# InterfacesA_RGMII_Ethernet.net
KiCad netlist of a schematic drawn in Altium Designer
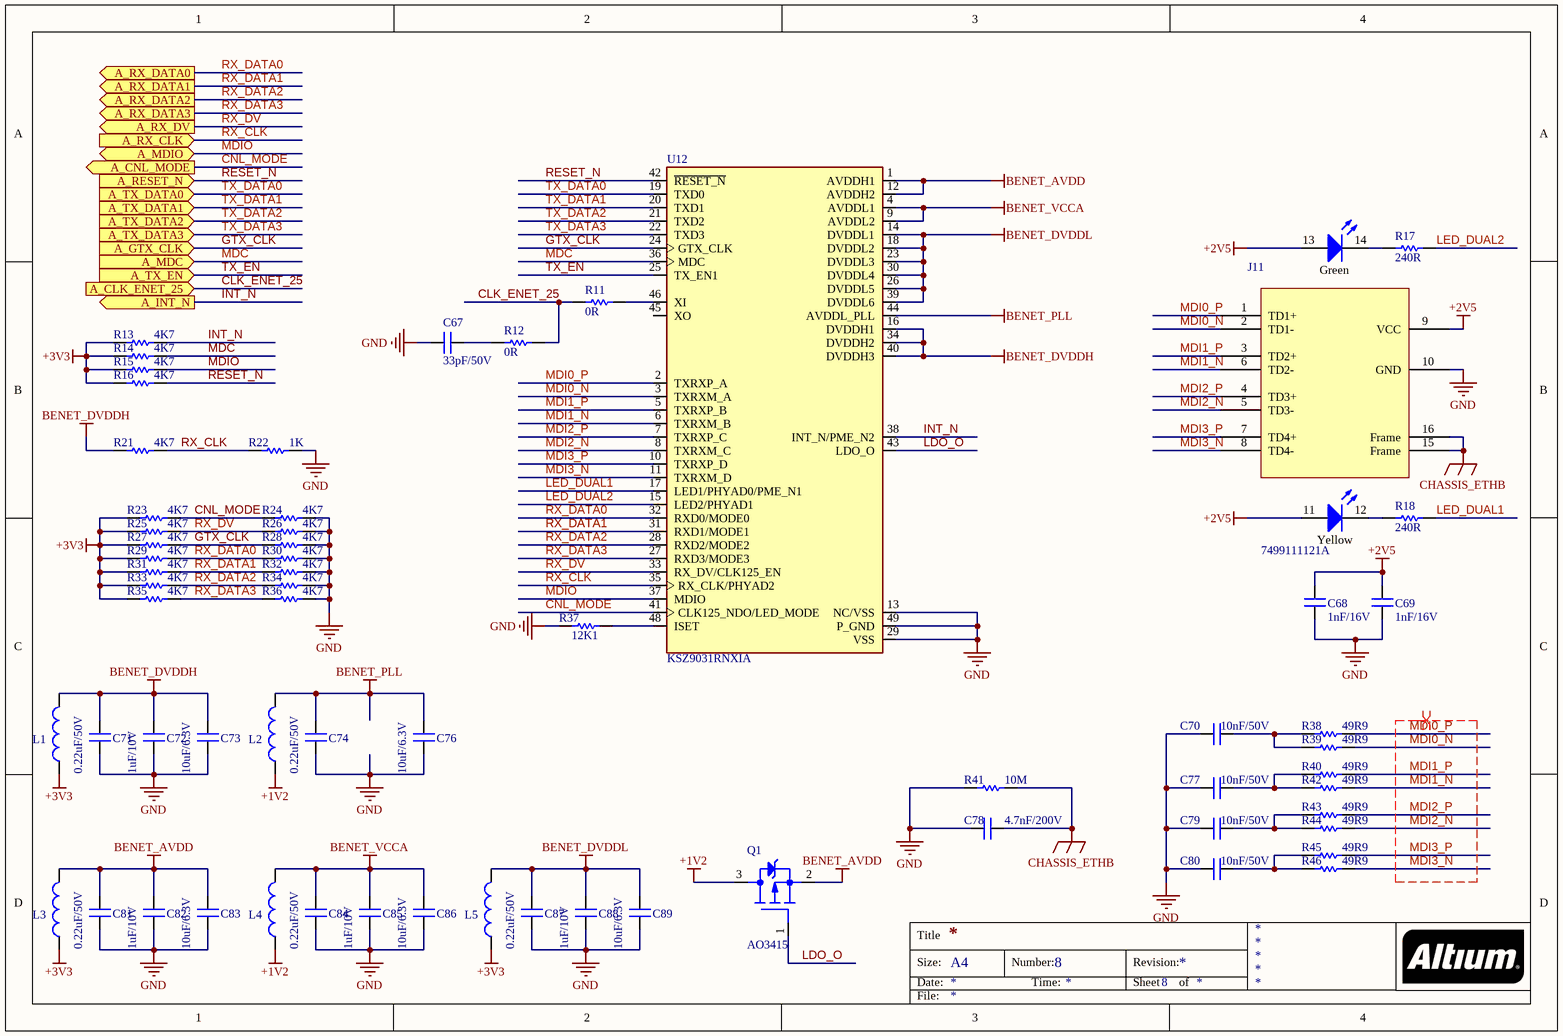
[diagram p0: InterfacesA_RGMII_Ethernet.SchDoc]

(export (version "E")
  (design (tool "Eeschema 10.0.6"))
  (components
    (comp (ref "C67")
      (value "33pF/50V")
      (footprint "CAP_0805")
      (fields (field (name "Comment") "CAP_0805"))
      (libsource (lib "AdapterLib") (part "CAP_0805"))
    )
    (comp (ref "C68")
      (value "1nF/16V")
      (footprint "CAP_0805")
      (fields (field (name "Comment") "CAP_0805"))
      (libsource (lib "AdapterLib") (part "CAP_0805"))
    )
    (comp (ref "C69")
      (value "1nF/16V")
      (footprint "CAP_0805")
      (fields (field (name "Comment") "CAP_0805"))
      (libsource (lib "AdapterLib") (part "CAP_0805"))
    )
    (comp (ref "C70")
      (value "10nF/50V")
      (footprint "CAP_0805")
      (fields (field (name "Comment") "CAP_0805"))
      (libsource (lib "AdapterLib") (part "CAP_0805"))
    )
    (comp (ref "C71")
      (value "0.22uF/50V")
      (footprint "CAP_0805")
      (fields (field (name "Comment") "CAP_0805"))
      (libsource (lib "AdapterLib") (part "CAP_0805"))
    )
    (comp (ref "C72")
      (value "1uF/10V")
      (footprint "CAP_0805")
      (fields (field (name "Comment") "CAP_0805"))
      (libsource (lib "AdapterLib") (part "CAP_0805"))
    )
    (comp (ref "C73")
      (value "10uF/6.3V")
      (footprint "CAP_0805")
      (fields (field (name "Comment") "CAP_0805"))
      (libsource (lib "AdapterLib") (part "CAP_0805"))
    )
    (comp (ref "C74")
      (value "0.22uF/50V")
      (footprint "CAP_0805")
      (fields (field (name "Comment") "CAP_0805"))
      (libsource (lib "AdapterLib") (part "CAP_0805"))
    )
    (comp (ref "C76")
      (value "10uF/6.3V")
      (footprint "CAP_0805")
      (fields (field (name "Comment") "CAP_0805"))
      (libsource (lib "AdapterLib") (part "CAP_0805"))
    )
    (comp (ref "C77")
      (value "10nF/50V")
      (footprint "CAP_0805")
      (fields (field (name "Comment") "CAP_0805"))
      (libsource (lib "AdapterLib") (part "CAP_0805"))
    )
    (comp (ref "C78")
      (value "4.7nF/200V")
      (footprint "CAP_0805")
      (fields (field (name "Comment") "CAP_0805"))
      (libsource (lib "AdapterLib") (part "CAP_0805"))
    )
    (comp (ref "C79")
      (value "10nF/50V")
      (footprint "CAP_0805")
      (fields (field (name "Comment") "CAP_0805"))
      (libsource (lib "AdapterLib") (part "CAP_0805"))
    )
    (comp (ref "C80")
      (value "10nF/50V")
      (footprint "CAP_0805")
      (fields (field (name "Comment") "CAP_0805"))
      (libsource (lib "AdapterLib") (part "CAP_0805"))
    )
    (comp (ref "C81")
      (value "0.22uF/50V")
      (footprint "CAP_0805")
      (fields (field (name "Comment") "CAP_0805"))
      (libsource (lib "AdapterLib") (part "CAP_0805"))
    )
    (comp (ref "C82")
      (value "1uF/10V")
      (footprint "CAP_0805")
      (fields (field (name "Comment") "CAP_0805"))
      (libsource (lib "AdapterLib") (part "CAP_0805"))
    )
    (comp (ref "C83")
      (value "10uF/6.3V")
      (footprint "CAP_0805")
      (fields (field (name "Comment") "CAP_0805"))
      (libsource (lib "AdapterLib") (part "CAP_0805"))
    )
    (comp (ref "C84")
      (value "0.22uF/50V")
      (footprint "CAP_0805")
      (fields (field (name "Comment") "CAP_0805"))
      (libsource (lib "AdapterLib") (part "CAP_0805"))
    )
    (comp (ref "C85")
      (value "1uF/10V")
      (footprint "CAP_0805")
      (fields (field (name "Comment") "CAP_0805"))
      (libsource (lib "AdapterLib") (part "CAP_0805"))
    )
    (comp (ref "C86")
      (value "10uF/6.3V")
      (footprint "CAP_0805")
      (fields (field (name "Comment") "CAP_0805"))
      (libsource (lib "AdapterLib") (part "CAP_0805"))
    )
    (comp (ref "C87")
      (value "0.22uF/50V")
      (footprint "CAP_0805")
      (fields (field (name "Comment") "CAP_0805"))
      (libsource (lib "AdapterLib") (part "CAP_0805"))
    )
    (comp (ref "C88")
      (value "1uF/10V")
      (footprint "CAP_0805")
      (fields (field (name "Comment") "CAP_0805"))
      (libsource (lib "AdapterLib") (part "CAP_0805"))
    )
    (comp (ref "C89")
      (value "10uF/6.3V")
      (footprint "CAP_0805")
      (fields (field (name "Comment") "CAP_0805"))
      (libsource (lib "AdapterLib") (part "CAP_0805"))
    )
    (comp (ref "J11")
      (value "7499111121A")
      (footprint "7499111121A")
      (libsource (lib "AdapterLib") (part "7499111121A"))
    )
    (comp (ref "L1")
      (value "IND_0805")
      (footprint "IND_0805")
      (libsource (lib "AdapterLib") (part "IND_0805"))
    )
    (comp (ref "L2")
      (value "IND_0805")
      (footprint "IND_0805")
      (libsource (lib "AdapterLib") (part "IND_0805"))
    )
    (comp (ref "L3")
      (value "IND_0805")
      (footprint "IND_0805")
      (libsource (lib "AdapterLib") (part "IND_0805"))
    )
    (comp (ref "L4")
      (value "IND_0805")
      (footprint "IND_0805")
      (libsource (lib "AdapterLib") (part "IND_0805"))
    )
    (comp (ref "L5")
      (value "IND_0805")
      (footprint "IND_0805")
      (libsource (lib "AdapterLib") (part "IND_0805"))
    )
    (comp (ref "Q1")
      (value "AO3415")
      (footprint "AO3415")
      (description "20V P-Channel MOSFET")
      (libsource (lib "AdapterLib") (part "AO3415"))
    )
    (comp (ref "R11")
      (value "0R")
      (footprint "RES_0805")
      (fields (field (name "Comment") "RES_0805"))
      (libsource (lib "AdapterLib") (part "RES_0805"))
    )
    (comp (ref "R12")
      (value "0R")
      (footprint "RES_0805")
      (fields (field (name "Comment") "RES_0805"))
      (libsource (lib "AdapterLib") (part "RES_0805"))
    )
    (comp (ref "R13")
      (value "4K7")
      (footprint "RES_0805")
      (fields (field (name "Comment") "RES_0805"))
      (libsource (lib "AdapterLib") (part "RES_0805"))
    )
    (comp (ref "R14")
      (value "4K7")
      (footprint "RES_0805")
      (fields (field (name "Comment") "RES_0805"))
      (libsource (lib "AdapterLib") (part "RES_0805"))
    )
    (comp (ref "R15")
      (value "4K7")
      (footprint "RES_0805")
      (fields (field (name "Comment") "RES_0805"))
      (libsource (lib "AdapterLib") (part "RES_0805"))
    )
    (comp (ref "R16")
      (value "4K7")
      (footprint "RES_0805")
      (fields (field (name "Comment") "RES_0805"))
      (libsource (lib "AdapterLib") (part "RES_0805"))
    )
    (comp (ref "R17")
      (value "240R")
      (footprint "RES_0805")
      (fields (field (name "Comment") "RES_0805"))
      (libsource (lib "AdapterLib") (part "RES_0805"))
    )
    (comp (ref "R18")
      (value "240R")
      (footprint "RES_0805")
      (fields (field (name "Comment") "RES_0805"))
      (libsource (lib "AdapterLib") (part "RES_0805"))
    )
    (comp (ref "R21")
      (value "4K7")
      (footprint "RES_0805")
      (fields (field (name "Comment") "RES_0805"))
      (libsource (lib "AdapterLib") (part "RES_0805"))
    )
    (comp (ref "R22")
      (value "1K")
      (footprint "RES_0805")
      (fields (field (name "Comment") "RES_0805"))
      (libsource (lib "AdapterLib") (part "RES_0805"))
    )
    (comp (ref "R23")
      (value "4K7")
      (footprint "RES_0805")
      (fields (field (name "Comment") "RES_0805"))
      (libsource (lib "AdapterLib") (part "RES_0805"))
    )
    (comp (ref "R24")
      (value "4K7")
      (footprint "RES_0805")
      (fields (field (name "Comment") "RES_0805"))
      (libsource (lib "AdapterLib") (part "RES_0805"))
    )
    (comp (ref "R25")
      (value "4K7")
      (footprint "RES_0805")
      (fields (field (name "Comment") "RES_0805"))
      (libsource (lib "AdapterLib") (part "RES_0805"))
    )
    (comp (ref "R26")
      (value "4K7")
      (footprint "RES_0805")
      (fields (field (name "Comment") "RES_0805"))
      (libsource (lib "AdapterLib") (part "RES_0805"))
    )
    (comp (ref "R27")
      (value "4K7")
      (footprint "RES_0805")
      (fields (field (name "Comment") "RES_0805"))
      (libsource (lib "AdapterLib") (part "RES_0805"))
    )
    (comp (ref "R28")
      (value "4K7")
      (footprint "RES_0805")
      (fields (field (name "Comment") "RES_0805"))
      (libsource (lib "AdapterLib") (part "RES_0805"))
    )
    (comp (ref "R29")
      (value "4K7")
      (footprint "RES_0805")
      (fields (field (name "Comment") "RES_0805"))
      (libsource (lib "AdapterLib") (part "RES_0805"))
    )
    (comp (ref "R30")
      (value "4K7")
      (footprint "RES_0805")
      (fields (field (name "Comment") "RES_0805"))
      (libsource (lib "AdapterLib") (part "RES_0805"))
    )
    (comp (ref "R31")
      (value "4K7")
      (footprint "RES_0805")
      (fields (field (name "Comment") "RES_0805"))
      (libsource (lib "AdapterLib") (part "RES_0805"))
    )
    (comp (ref "R32")
      (value "4K7")
      (footprint "RES_0805")
      (fields (field (name "Comment") "RES_0805"))
      (libsource (lib "AdapterLib") (part "RES_0805"))
    )
    (comp (ref "R33")
      (value "4K7")
      (footprint "RES_0805")
      (fields (field (name "Comment") "RES_0805"))
      (libsource (lib "AdapterLib") (part "RES_0805"))
    )
    (comp (ref "R34")
      (value "4K7")
      (footprint "RES_0805")
      (fields (field (name "Comment") "RES_0805"))
      (libsource (lib "AdapterLib") (part "RES_0805"))
    )
    (comp (ref "R35")
      (value "4K7")
      (footprint "RES_0805")
      (fields (field (name "Comment") "RES_0805"))
      (libsource (lib "AdapterLib") (part "RES_0805"))
    )
    (comp (ref "R36")
      (value "4K7")
      (footprint "RES_0805")
      (fields (field (name "Comment") "RES_0805"))
      (libsource (lib "AdapterLib") (part "RES_0805"))
    )
    (comp (ref "R37")
      (value "12K1")
      (footprint "RES_0805")
      (fields (field (name "Comment") "RES_0805"))
      (libsource (lib "AdapterLib") (part "RES_0805"))
    )
    (comp (ref "R38")
      (value "49R9")
      (footprint "RES_0805")
      (fields (field (name "Comment") "RES_0805"))
      (libsource (lib "AdapterLib") (part "RES_0805"))
    )
    (comp (ref "R39")
      (value "49R9")
      (footprint "RES_0805")
      (fields (field (name "Comment") "RES_0805"))
      (libsource (lib "AdapterLib") (part "RES_0805"))
    )
    (comp (ref "R40")
      (value "49R9")
      (footprint "RES_0805")
      (fields (field (name "Comment") "RES_0805"))
      (libsource (lib "AdapterLib") (part "RES_0805"))
    )
    (comp (ref "R41")
      (value "10M")
      (footprint "RES_0805")
      (fields (field (name "Comment") "RES_0805"))
      (libsource (lib "AdapterLib") (part "RES_0805"))
    )
    (comp (ref "R42")
      (value "49R9")
      (footprint "RES_0805")
      (fields (field (name "Comment") "RES_0805"))
      (libsource (lib "AdapterLib") (part "RES_0805"))
    )
    (comp (ref "R43")
      (value "49R9")
      (footprint "RES_0805")
      (fields (field (name "Comment") "RES_0805"))
      (libsource (lib "AdapterLib") (part "RES_0805"))
    )
    (comp (ref "R44")
      (value "49R9")
      (footprint "RES_0805")
      (fields (field (name "Comment") "RES_0805"))
      (libsource (lib "AdapterLib") (part "RES_0805"))
    )
    (comp (ref "R45")
      (value "49R9")
      (footprint "RES_0805")
      (fields (field (name "Comment") "RES_0805"))
      (libsource (lib "AdapterLib") (part "RES_0805"))
    )
    (comp (ref "R46")
      (value "49R9")
      (footprint "RES_0805")
      (fields (field (name "Comment") "RES_0805"))
      (libsource (lib "AdapterLib") (part "RES_0805"))
    )
    (comp (ref "U12")
      (value "KSZ9031RNXIA")
      (footprint "AdapterLib:KSZ9031RNXIA")
      (description "4/4 Transceiver Full Ethernet 48-QFN _7x7_")
      (fields (field (name "DIGI-KEY_PART_NUMBER") "KSZ9031RNXIA-TR-ND") (field (name "MF") "Microchip"))
      (libsource (lib "AdapterLib") (part "KSZ9031RNXIA"))
    )
  )
  (nets
    (net (code "1") (name "+1V2") (class "Default")
      (node (ref "L2") (pin "1") (pinfunction "1_1") (pintype "passive"))
      (node (ref "L4") (pin "1") (pinfunction "1_1") (pintype "passive"))
      (node (ref "Q1") (pin "3") (pinfunction "D_3") (pintype "passive"))
    )
    (net (code "2") (name "+2V5") (class "Default")
      (node (ref "C68") (pin "2") (pinfunction "2_2") (pintype "passive"))
      (node (ref "C69") (pin "2") (pinfunction "2_2") (pintype "passive"))
      (node (ref "J11") (pin "11") (pinfunction "A_11") (pintype "passive"))
      (node (ref "J11") (pin "13") (pinfunction "A_13") (pintype "passive"))
      (node (ref "J11") (pin "9") (pinfunction "VCC_9") (pintype "passive"))
    )
    (net (code "3") (name "+3V3") (class "Default")
      (node (ref "L1") (pin "1") (pinfunction "1_1") (pintype "passive"))
      (node (ref "L3") (pin "1") (pinfunction "1_1") (pintype "passive"))
      (node (ref "L5") (pin "1") (pinfunction "1_1") (pintype "passive"))
      (node (ref "R13") (pin "2") (pinfunction "2_2") (pintype "passive"))
      (node (ref "R14") (pin "2") (pinfunction "2_2") (pintype "passive"))
      (node (ref "R15") (pin "2") (pinfunction "2_2") (pintype "passive"))
      (node (ref "R16") (pin "2") (pinfunction "2_2") (pintype "passive"))
      (node (ref "R23") (pin "2") (pinfunction "2_2") (pintype "passive"))
      (node (ref "R25") (pin "2") (pinfunction "2_2") (pintype "passive"))
      (node (ref "R27") (pin "2") (pinfunction "2_2") (pintype "passive"))
      (node (ref "R29") (pin "2") (pinfunction "2_2") (pintype "passive"))
      (node (ref "R31") (pin "2") (pinfunction "2_2") (pintype "passive"))
      (node (ref "R33") (pin "2") (pinfunction "2_2") (pintype "passive"))
      (node (ref "R35") (pin "2") (pinfunction "2_2") (pintype "passive"))
    )
    (net (code "4") (name "/CLK_ENET_25") (class "Default")
      (node (ref "R11") (pin "2") (pinfunction "2_2") (pintype "passive"))
      (node (ref "R12") (pin "2") (pinfunction "2_2") (pintype "passive"))
    )
    (net (code "5") (name "/CNL_MODE") (class "Default")
      (node (ref "R23") (pin "1") (pinfunction "1_1") (pintype "passive"))
      (node (ref "R24") (pin "2") (pinfunction "2_2") (pintype "passive"))
      (node (ref "U12") (pin "41") (pinfunction "CLK125_NDO/LED_MODE_41") (pintype "passive"))
    )
    (net (code "6") (name "/GTX_CLK") (class "Default")
      (node (ref "R27") (pin "1") (pinfunction "1_1") (pintype "passive"))
      (node (ref "R28") (pin "2") (pinfunction "2_2") (pintype "passive"))
      (node (ref "U12") (pin "24") (pinfunction "GTX_CLK_24") (pintype "passive"))
    )
    (net (code "7") (name "/INT_N") (class "Default")
      (node (ref "R13") (pin "1") (pinfunction "1_1") (pintype "passive"))
      (node (ref "U12") (pin "38") (pinfunction "INT_N/PME_N2_38") (pintype "passive"))
    )
    (net (code "8") (name "/LDO_O") (class "Default")
      (node (ref "Q1") (pin "1") (pinfunction "G_1") (pintype "passive"))
      (node (ref "U12") (pin "43") (pinfunction "LDO_O_43") (pintype "passive"))
    )
    (net (code "9") (name "/LED_DUAL1") (class "Default")
      (node (ref "R18") (pin "2") (pinfunction "2_2") (pintype "passive"))
      (node (ref "U12") (pin "17") (pinfunction "LED1/PHYAD0/PME_N1_17") (pintype "passive"))
    )
    (net (code "10") (name "/LED_DUAL2") (class "Default")
      (node (ref "R17") (pin "2") (pinfunction "2_2") (pintype "passive"))
      (node (ref "U12") (pin "15") (pinfunction "LED2/PHYAD1_15") (pintype "passive"))
    )
    (net (code "11") (name "/MDC") (class "Default")
      (node (ref "R14") (pin "1") (pinfunction "1_1") (pintype "passive"))
      (node (ref "U12") (pin "36") (pinfunction "MDC_36") (pintype "passive"))
    )
    (net (code "12") (name "/MDI0_N") (class "Default")
      (node (ref "J11") (pin "2") (pinfunction "TD1-_2") (pintype "passive"))
      (node (ref "R39") (pin "2") (pinfunction "2_2") (pintype "passive"))
      (node (ref "U12") (pin "3") (pinfunction "TXRXM_A_3") (pintype "passive"))
    )
    (net (code "13") (name "/MDI0_P") (class "Default")
      (node (ref "J11") (pin "1") (pinfunction "TD1+_1") (pintype "passive"))
      (node (ref "R38") (pin "2") (pinfunction "2_2") (pintype "passive"))
      (node (ref "U12") (pin "2") (pinfunction "TXRXP_A_2") (pintype "passive"))
    )
    (net (code "14") (name "/MDI1_N") (class "Default")
      (node (ref "J11") (pin "6") (pinfunction "TD2-_6") (pintype "passive"))
      (node (ref "R42") (pin "2") (pinfunction "2_2") (pintype "passive"))
      (node (ref "U12") (pin "6") (pinfunction "TXRXM_B_6") (pintype "passive"))
    )
    (net (code "15") (name "/MDI1_P") (class "Default")
      (node (ref "J11") (pin "3") (pinfunction "TD2+_3") (pintype "passive"))
      (node (ref "R40") (pin "2") (pinfunction "2_2") (pintype "passive"))
      (node (ref "U12") (pin "5") (pinfunction "TXRXP_B_5") (pintype "passive"))
    )
    (net (code "16") (name "/MDI2_N") (class "Default")
      (node (ref "J11") (pin "5") (pinfunction "TD3-_5") (pintype "passive"))
      (node (ref "R44") (pin "2") (pinfunction "2_2") (pintype "passive"))
      (node (ref "U12") (pin "8") (pinfunction "TXRXM_C_8") (pintype "passive"))
    )
    (net (code "17") (name "/MDI2_P") (class "Default")
      (node (ref "J11") (pin "4") (pinfunction "TD3+_4") (pintype "passive"))
      (node (ref "R43") (pin "2") (pinfunction "2_2") (pintype "passive"))
      (node (ref "U12") (pin "7") (pinfunction "TXRXP_C_7") (pintype "passive"))
    )
    (net (code "18") (name "/MDI3_N") (class "Default")
      (node (ref "J11") (pin "8") (pinfunction "TD4-_8") (pintype "passive"))
      (node (ref "R46") (pin "2") (pinfunction "2_2") (pintype "passive"))
      (node (ref "U12") (pin "11") (pinfunction "TXRXM_D_11") (pintype "passive"))
    )
    (net (code "19") (name "/MDI3_P") (class "Default")
      (node (ref "J11") (pin "7") (pinfunction "TD4+_7") (pintype "passive"))
      (node (ref "R45") (pin "2") (pinfunction "2_2") (pintype "passive"))
      (node (ref "U12") (pin "10") (pinfunction "TXRXP_D_10") (pintype "passive"))
    )
    (net (code "20") (name "/MDIO") (class "Default")
      (node (ref "R15") (pin "1") (pinfunction "1_1") (pintype "passive"))
      (node (ref "U12") (pin "37") (pinfunction "MDIO_37") (pintype "passive"))
    )
    (net (code "21") (name "/RESET_N") (class "Default")
      (node (ref "R16") (pin "1") (pinfunction "1_1") (pintype "passive"))
      (node (ref "U12") (pin "42") (pinfunction "~{RESET_N}_42") (pintype "passive"))
    )
    (net (code "22") (name "/RX_CLK") (class "Default")
      (node (ref "R21") (pin "1") (pinfunction "1_1") (pintype "passive"))
      (node (ref "R22") (pin "2") (pinfunction "2_2") (pintype "passive"))
      (node (ref "U12") (pin "35") (pinfunction "RX_CLK/PHYAD2_35") (pintype "passive"))
    )
    (net (code "23") (name "/RX_DATA0") (class "Default")
      (node (ref "R29") (pin "1") (pinfunction "1_1") (pintype "passive"))
      (node (ref "R30") (pin "2") (pinfunction "2_2") (pintype "passive"))
      (node (ref "U12") (pin "32") (pinfunction "RXD0/MODE0_32") (pintype "passive"))
    )
    (net (code "24") (name "/RX_DATA1") (class "Default")
      (node (ref "R31") (pin "1") (pinfunction "1_1") (pintype "passive"))
      (node (ref "R32") (pin "2") (pinfunction "2_2") (pintype "passive"))
      (node (ref "U12") (pin "31") (pinfunction "RXD1/MODE1_31") (pintype "passive"))
    )
    (net (code "25") (name "/RX_DATA2") (class "Default")
      (node (ref "R33") (pin "1") (pinfunction "1_1") (pintype "passive"))
      (node (ref "R34") (pin "2") (pinfunction "2_2") (pintype "passive"))
      (node (ref "U12") (pin "28") (pinfunction "RXD2/MODE2_28") (pintype "passive"))
    )
    (net (code "26") (name "/RX_DATA3") (class "Default")
      (node (ref "R35") (pin "1") (pinfunction "1_1") (pintype "passive"))
      (node (ref "R36") (pin "2") (pinfunction "2_2") (pintype "passive"))
      (node (ref "U12") (pin "27") (pinfunction "RXD3/MODE3_27") (pintype "passive"))
    )
    (net (code "27") (name "/RX_DV") (class "Default")
      (node (ref "R25") (pin "1") (pinfunction "1_1") (pintype "passive"))
      (node (ref "R26") (pin "2") (pinfunction "2_2") (pintype "passive"))
      (node (ref "U12") (pin "33") (pinfunction "RX_DV/CLK125_EN_33") (pintype "passive"))
    )
    (net (code "28") (name "/TX_DATA0") (class "Default")
      (node (ref "U12") (pin "19") (pinfunction "TXD0_19") (pintype "passive"))
    )
    (net (code "29") (name "/TX_DATA1") (class "Default")
      (node (ref "U12") (pin "20") (pinfunction "TXD1_20") (pintype "passive"))
    )
    (net (code "30") (name "/TX_DATA2") (class "Default")
      (node (ref "U12") (pin "21") (pinfunction "TXD2_21") (pintype "passive"))
    )
    (net (code "31") (name "/TX_DATA3") (class "Default")
      (node (ref "U12") (pin "22") (pinfunction "TXD3_22") (pintype "passive"))
    )
    (net (code "32") (name "/TX_EN") (class "Default")
      (node (ref "U12") (pin "25") (pinfunction "TX_EN1_25") (pintype "passive"))
    )
    (net (code "33") (name "BENET_AVDD") (class "Default")
      (node (ref "C81") (pin "2") (pinfunction "2_2") (pintype "passive"))
      (node (ref "C82") (pin "2") (pinfunction "2_2") (pintype "passive"))
      (node (ref "C83") (pin "2") (pinfunction "2_2") (pintype "passive"))
      (node (ref "L3") (pin "2") (pinfunction "2_2") (pintype "passive"))
      (node (ref "Q1") (pin "2") (pinfunction "S_2") (pintype "passive"))
      (node (ref "U12") (pin "1") (pinfunction "AVDDH1_1") (pintype "passive"))
      (node (ref "U12") (pin "12") (pinfunction "AVDDH2_12") (pintype "passive"))
    )
    (net (code "34") (name "BENET_DVDDH") (class "Default")
      (node (ref "C71") (pin "2") (pinfunction "2_2") (pintype "passive"))
      (node (ref "C72") (pin "2") (pinfunction "2_2") (pintype "passive"))
      (node (ref "C73") (pin "2") (pinfunction "2_2") (pintype "passive"))
      (node (ref "L1") (pin "2") (pinfunction "2_2") (pintype "passive"))
      (node (ref "R21") (pin "2") (pinfunction "2_2") (pintype "passive"))
      (node (ref "U12") (pin "16") (pinfunction "DVDDH1_16") (pintype "passive"))
      (node (ref "U12") (pin "34") (pinfunction "DVDDH2_34") (pintype "passive"))
      (node (ref "U12") (pin "40") (pinfunction "DVDDH3_40") (pintype "passive"))
    )
    (net (code "35") (name "BENET_DVDDL") (class "Default")
      (node (ref "C87") (pin "2") (pinfunction "2_2") (pintype "passive"))
      (node (ref "C88") (pin "2") (pinfunction "2_2") (pintype "passive"))
      (node (ref "C89") (pin "2") (pinfunction "2_2") (pintype "passive"))
      (node (ref "L5") (pin "2") (pinfunction "2_2") (pintype "passive"))
      (node (ref "U12") (pin "14") (pinfunction "DVDDL1_14") (pintype "passive"))
      (node (ref "U12") (pin "18") (pinfunction "DVDDL2_18") (pintype "passive"))
      (node (ref "U12") (pin "23") (pinfunction "DVDDL3_23") (pintype "passive"))
      (node (ref "U12") (pin "26") (pinfunction "DVDDL5_26") (pintype "passive"))
      (node (ref "U12") (pin "30") (pinfunction "DVDDL4_30") (pintype "passive"))
      (node (ref "U12") (pin "39") (pinfunction "DVDDL6_39") (pintype "passive"))
    )
    (net (code "36") (name "BENET_PLL") (class "Default")
      (node (ref "C74") (pin "2") (pinfunction "2_2") (pintype "passive"))
      (node (ref "C76") (pin "2") (pinfunction "2_2") (pintype "passive"))
      (node (ref "L2") (pin "2") (pinfunction "2_2") (pintype "passive"))
      (node (ref "U12") (pin "44") (pinfunction "AVDDL_PLL_44") (pintype "passive"))
    )
    (net (code "37") (name "BENET_VCCA") (class "Default")
      (node (ref "C84") (pin "2") (pinfunction "2_2") (pintype "passive"))
      (node (ref "C85") (pin "2") (pinfunction "2_2") (pintype "passive"))
      (node (ref "C86") (pin "2") (pinfunction "2_2") (pintype "passive"))
      (node (ref "L4") (pin "2") (pinfunction "2_2") (pintype "passive"))
      (node (ref "U12") (pin "4") (pinfunction "AVDDL1_4") (pintype "passive"))
      (node (ref "U12") (pin "9") (pinfunction "AVDDL2_9") (pintype "passive"))
    )
    (net (code "38") (name "CHASSIS_ETHB") (class "Default")
      (node (ref "C78") (pin "1") (pinfunction "1_1") (pintype "passive"))
      (node (ref "J11") (pin "15") (pinfunction "Frame_15") (pintype "passive"))
      (node (ref "J11") (pin "16") (pinfunction "Frame_16") (pintype "passive"))
      (node (ref "R41") (pin "1") (pinfunction "1_1") (pintype "passive"))
    )
    (net (code "39") (name "GND") (class "Default")
      (node (ref "C67") (pin "2") (pinfunction "2_2") (pintype "passive"))
      (node (ref "C68") (pin "1") (pinfunction "1_1") (pintype "passive"))
      (node (ref "C69") (pin "1") (pinfunction "1_1") (pintype "passive"))
      (node (ref "C70") (pin "2") (pinfunction "2_2") (pintype "passive"))
      (node (ref "C71") (pin "1") (pinfunction "1_1") (pintype "passive"))
      (node (ref "C72") (pin "1") (pinfunction "1_1") (pintype "passive"))
      (node (ref "C73") (pin "1") (pinfunction "1_1") (pintype "passive"))
      (node (ref "C74") (pin "1") (pinfunction "1_1") (pintype "passive"))
      (node (ref "C76") (pin "1") (pinfunction "1_1") (pintype "passive"))
      (node (ref "C77") (pin "2") (pinfunction "2_2") (pintype "passive"))
      (node (ref "C78") (pin "2") (pinfunction "2_2") (pintype "passive"))
      (node (ref "C79") (pin "2") (pinfunction "2_2") (pintype "passive"))
      (node (ref "C80") (pin "2") (pinfunction "2_2") (pintype "passive"))
      (node (ref "C81") (pin "1") (pinfunction "1_1") (pintype "passive"))
      (node (ref "C82") (pin "1") (pinfunction "1_1") (pintype "passive"))
      (node (ref "C83") (pin "1") (pinfunction "1_1") (pintype "passive"))
      (node (ref "C84") (pin "1") (pinfunction "1_1") (pintype "passive"))
      (node (ref "C85") (pin "1") (pinfunction "1_1") (pintype "passive"))
      (node (ref "C86") (pin "1") (pinfunction "1_1") (pintype "passive"))
      (node (ref "C87") (pin "1") (pinfunction "1_1") (pintype "passive"))
      (node (ref "C88") (pin "1") (pinfunction "1_1") (pintype "passive"))
      (node (ref "C89") (pin "1") (pinfunction "1_1") (pintype "passive"))
      (node (ref "J11") (pin "10") (pinfunction "GND_10") (pintype "passive"))
      (node (ref "R22") (pin "1") (pinfunction "1_1") (pintype "passive"))
      (node (ref "R24") (pin "1") (pinfunction "1_1") (pintype "passive"))
      (node (ref "R26") (pin "1") (pinfunction "1_1") (pintype "passive"))
      (node (ref "R28") (pin "1") (pinfunction "1_1") (pintype "passive"))
      (node (ref "R30") (pin "1") (pinfunction "1_1") (pintype "passive"))
      (node (ref "R32") (pin "1") (pinfunction "1_1") (pintype "passive"))
      (node (ref "R34") (pin "1") (pinfunction "1_1") (pintype "passive"))
      (node (ref "R36") (pin "1") (pinfunction "1_1") (pintype "passive"))
      (node (ref "R37") (pin "1") (pinfunction "1_1") (pintype "passive"))
      (node (ref "R41") (pin "2") (pinfunction "2_2") (pintype "passive"))
      (node (ref "U12") (pin "13") (pinfunction "NC/VSS_13") (pintype "passive"))
      (node (ref "U12") (pin "29") (pinfunction "VSS_29") (pintype "passive"))
      (node (ref "U12") (pin "49") (pinfunction "P_GND_49") (pintype "passive"))
    )
    (net (code "40") (name "Net-(C67-Pad1)") (class "Default")
      (node (ref "C67") (pin "1") (pinfunction "1_1") (pintype "passive"))
      (node (ref "R12") (pin "1") (pinfunction "1_1") (pintype "passive"))
    )
    (net (code "41") (name "Net-(C70-Pad1)") (class "Default")
      (node (ref "C70") (pin "1") (pinfunction "1_1") (pintype "passive"))
      (node (ref "R38") (pin "1") (pinfunction "1_1") (pintype "passive"))
      (node (ref "R39") (pin "1") (pinfunction "1_1") (pintype "passive"))
    )
    (net (code "42") (name "Net-(C77-Pad1)") (class "Default")
      (node (ref "C77") (pin "1") (pinfunction "1_1") (pintype "passive"))
      (node (ref "R40") (pin "1") (pinfunction "1_1") (pintype "passive"))
      (node (ref "R42") (pin "1") (pinfunction "1_1") (pintype "passive"))
    )
    (net (code "43") (name "Net-(C79-Pad1)") (class "Default")
      (node (ref "C79") (pin "1") (pinfunction "1_1") (pintype "passive"))
      (node (ref "R43") (pin "1") (pinfunction "1_1") (pintype "passive"))
      (node (ref "R44") (pin "1") (pinfunction "1_1") (pintype "passive"))
    )
    (net (code "44") (name "Net-(C80-Pad1)") (class "Default")
      (node (ref "C80") (pin "1") (pinfunction "1_1") (pintype "passive"))
      (node (ref "R45") (pin "1") (pinfunction "1_1") (pintype "passive"))
      (node (ref "R46") (pin "1") (pinfunction "1_1") (pintype "passive"))
    )
    (net (code "45") (name "Net-(J11-K-Pad12)") (class "Default")
      (node (ref "J11") (pin "12") (pinfunction "K_12") (pintype "passive"))
      (node (ref "R18") (pin "1") (pinfunction "1_1") (pintype "passive"))
    )
    (net (code "46") (name "Net-(J11-K-Pad14)") (class "Default")
      (node (ref "J11") (pin "14") (pinfunction "K_14") (pintype "passive"))
      (node (ref "R17") (pin "1") (pinfunction "1_1") (pintype "passive"))
    )
    (net (code "47") (name "Net-(U12-ISET)") (class "Default")
      (node (ref "R37") (pin "2") (pinfunction "2_2") (pintype "passive"))
      (node (ref "U12") (pin "48") (pinfunction "ISET_48") (pintype "passive"))
    )
    (net (code "48") (name "Net-(U12-XI)") (class "Default")
      (node (ref "R11") (pin "1") (pinfunction "1_1") (pintype "passive"))
      (node (ref "U12") (pin "46") (pinfunction "XI_46") (pintype "passive"))
    )
    (net (code "49") (name "unconnected-(U12-XO-Pad45)") (class "Default")
      (node (ref "U12") (pin "45") (pinfunction "XO_45") (pintype "passive"))
    )
  )
)
